# Control_Board_V2.net
KiCad netlist of a schematic drawn in EAGLE
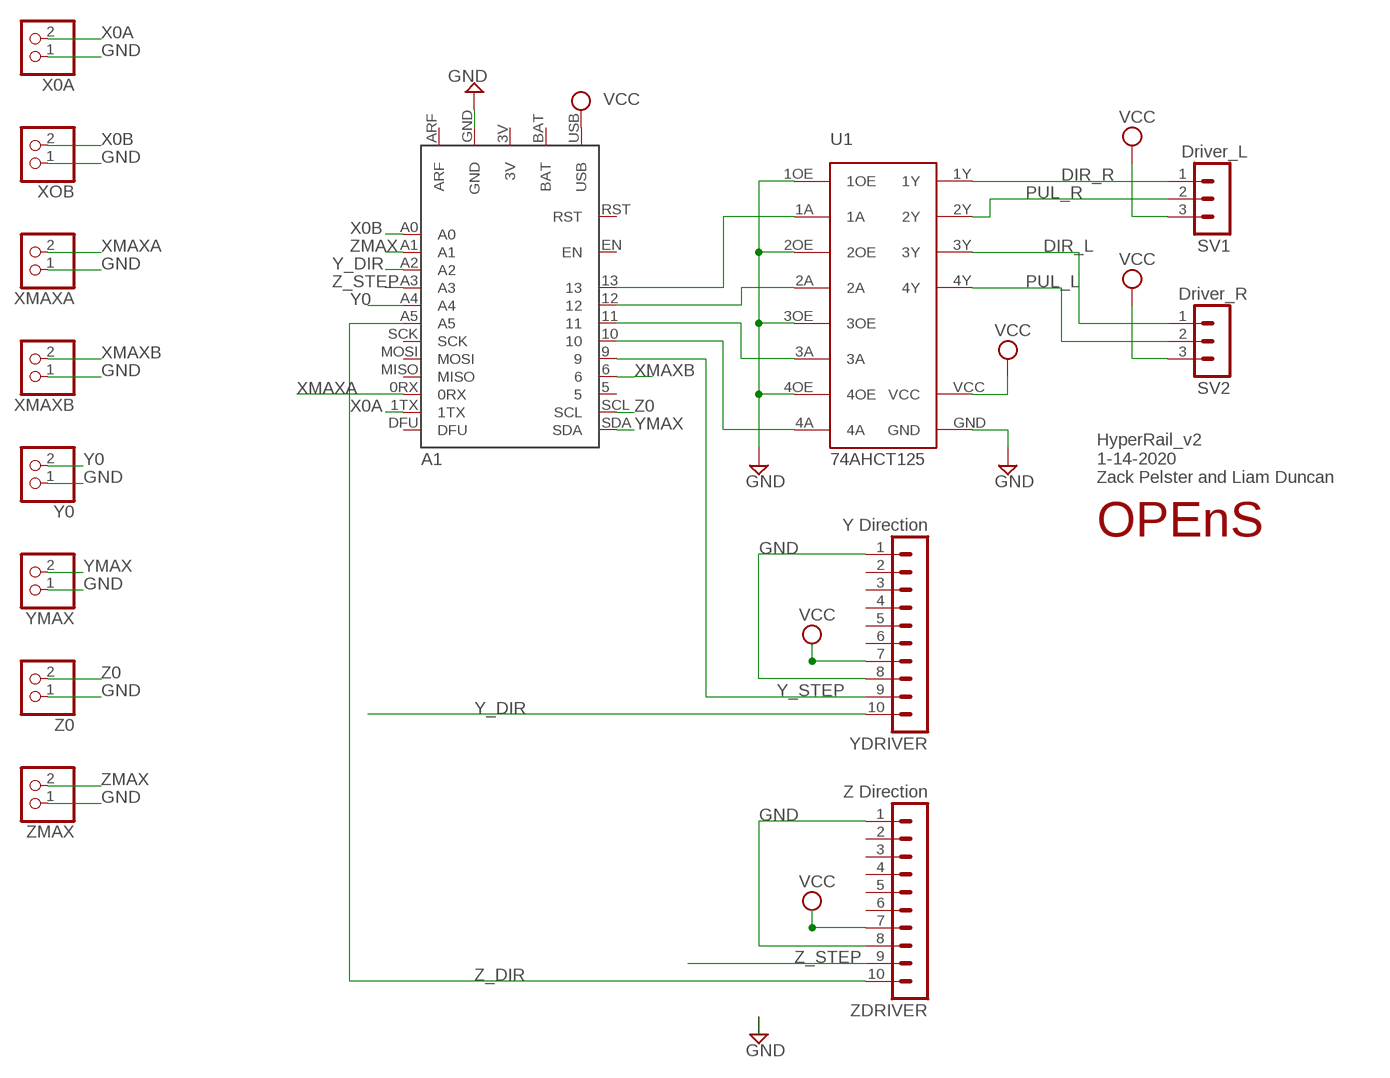
[diagram p0: schematic, sheet 1]

(export (version "E")
  (design (tool "Eeschema 10.0.6"))
  (components
    (comp (ref "A1")
      (value "FEATHER_BLUEFRUIT_M0")
      (footprint "eagle-import:FEATHER_BLUEFRUIT_M0")
      (libsource (lib "eagle-import") (part "FEATHER_BLUEFRUIT_M0"))
    )
    (comp (ref "SV1")
      (value "Driver_L")
      (footprint "eagle-import:MA03-1")
      (libsource (lib "eagle-import") (part "MA03-1"))
    )
    (comp (ref "SV2")
      (value "Driver_R")
      (footprint "eagle-import:MA03-1")
      (libsource (lib "eagle-import") (part "MA03-1"))
    )
    (comp (ref "U$1")
      (value "OPENS-LOGO")
      (footprint "eagle-import:OPENS-LOGO")
      (libsource (lib "eagle-import") (part "OPENS-LOGO"))
    )
    (comp (ref "U1")
      (value "74AHCT125")
      (footprint "eagle-import:74AHCT125")
      (libsource (lib "eagle-import") (part "74AHCT125"))
    )
    (comp (ref "X0A")
      (value "PINHD-1X2")
      (footprint "eagle-import:1X02")
      (libsource (lib "eagle-import") (part "PINHD-1X2"))
    )
    (comp (ref "XMAXA")
      (value "PINHD-1X2")
      (footprint "eagle-import:1X02")
      (libsource (lib "eagle-import") (part "PINHD-1X2"))
    )
    (comp (ref "XMAXB")
      (value "PINHD-1X2")
      (footprint "eagle-import:1X02")
      (libsource (lib "eagle-import") (part "PINHD-1X2"))
    )
    (comp (ref "XOB")
      (value "PINHD-1X2")
      (footprint "eagle-import:1X02")
      (libsource (lib "eagle-import") (part "PINHD-1X2"))
    )
    (comp (ref "Y0")
      (value "PINHD-1X2")
      (footprint "eagle-import:1X02")
      (libsource (lib "eagle-import") (part "PINHD-1X2"))
    )
    (comp (ref "YDRIVER")
      (value "Y Direction")
      (footprint "eagle-import:MA10-1")
      (libsource (lib "eagle-import") (part "MA10-1"))
    )
    (comp (ref "YMAX")
      (value "PINHD-1X2")
      (footprint "eagle-import:1X02")
      (libsource (lib "eagle-import") (part "PINHD-1X2"))
    )
    (comp (ref "Z0")
      (value "PINHD-1X2")
      (footprint "eagle-import:1X02")
      (libsource (lib "eagle-import") (part "PINHD-1X2"))
    )
    (comp (ref "ZDRIVER")
      (value "Z Direction")
      (footprint "eagle-import:MA10-1")
      (libsource (lib "eagle-import") (part "MA10-1"))
    )
    (comp (ref "ZMAX")
      (value "PINHD-1X2")
      (footprint "eagle-import:1X02")
      (libsource (lib "eagle-import") (part "PINHD-1X2"))
    )
  )
  (nets
    (net (code "1") (name "/3V") (class "Default")
      (node (ref "A1") (pin "3V") (pinfunction "3V_3V") (pintype "power_in"))
    )
    (net (code "2") (name "/BAT") (class "Default")
      (node (ref "A1") (pin "BAT") (pinfunction "BAT_BAT") (pintype "power_in"))
    )
    (net (code "3") (name "/DIR_L") (class "Default")
      (node (ref "SV2") (pin "1") (pinfunction "1_1") (pintype "passive"))
      (node (ref "U1") (pin "3Y") (pinfunction "3Y_3Y") (pintype "bidirectional"))
    )
    (net (code "4") (name "/DIR_R") (class "Default")
      (node (ref "SV1") (pin "1") (pinfunction "1_1") (pintype "passive"))
      (node (ref "U1") (pin "1Y") (pinfunction "1Y_1Y") (pintype "bidirectional"))
    )
    (net (code "5") (name "/PUL_L") (class "Default")
      (node (ref "SV2") (pin "2") (pinfunction "2_2") (pintype "passive"))
      (node (ref "U1") (pin "4Y") (pinfunction "4Y_4Y") (pintype "bidirectional"))
    )
    (net (code "6") (name "/PUL_R") (class "Default")
      (node (ref "SV1") (pin "2") (pinfunction "2_2") (pintype "passive"))
      (node (ref "U1") (pin "2Y") (pinfunction "2Y_2Y") (pintype "bidirectional"))
    )
    (net (code "7") (name "/X0A") (class "Default")
      (node (ref "A1") (pin "1TX") (pinfunction "1TX_1TX") (pintype "bidirectional"))
      (node (ref "X0A") (pin "2") (pinfunction "2_2") (pintype "passive"))
    )
    (net (code "8") (name "/X0B") (class "Default")
      (node (ref "A1") (pin "A0") (pinfunction "A0_A0") (pintype "bidirectional"))
      (node (ref "XOB") (pin "2") (pinfunction "2_2") (pintype "passive"))
    )
    (net (code "9") (name "/XMAXA") (class "Default")
      (node (ref "A1") (pin "0RX") (pinfunction "0RX_0RX") (pintype "bidirectional"))
      (node (ref "XMAXA") (pin "2") (pinfunction "2_2") (pintype "passive"))
    )
    (net (code "10") (name "/XMAXB") (class "Default")
      (node (ref "A1") (pin "6") (pinfunction "6_6") (pintype "bidirectional"))
      (node (ref "XMAXB") (pin "2") (pinfunction "2_2") (pintype "passive"))
    )
    (net (code "11") (name "/Y0") (class "Default")
      (node (ref "A1") (pin "A4") (pinfunction "A4_A4") (pintype "bidirectional"))
      (node (ref "Y0") (pin "2") (pinfunction "2_2") (pintype "passive"))
    )
    (net (code "12") (name "/YMAX") (class "Default")
      (node (ref "A1") (pin "SDA") (pinfunction "SDA_SDA") (pintype "bidirectional"))
      (node (ref "YMAX") (pin "2") (pinfunction "2_2") (pintype "passive"))
    )
    (net (code "13") (name "/Y_DIR") (class "Default")
      (node (ref "A1") (pin "A2") (pinfunction "A2_A2") (pintype "bidirectional"))
      (node (ref "YDRIVER") (pin "10") (pinfunction "10_10") (pintype "passive"))
    )
    (net (code "14") (name "/Y_STEP") (class "Default")
      (node (ref "A1") (pin "9") (pinfunction "9_9") (pintype "bidirectional"))
      (node (ref "YDRIVER") (pin "9") (pinfunction "9_9") (pintype "passive"))
    )
    (net (code "15") (name "/Z0") (class "Default")
      (node (ref "A1") (pin "SCL") (pinfunction "SCL_SCL") (pintype "bidirectional"))
      (node (ref "Z0") (pin "2") (pinfunction "2_2") (pintype "passive"))
    )
    (net (code "16") (name "/ZMAX") (class "Default")
      (node (ref "A1") (pin "A1") (pinfunction "A1_A1") (pintype "bidirectional"))
      (node (ref "ZMAX") (pin "2") (pinfunction "2_2") (pintype "passive"))
    )
    (net (code "17") (name "/Z_DIR") (class "Default")
      (node (ref "A1") (pin "A5") (pinfunction "A5_A5") (pintype "bidirectional"))
      (node (ref "ZDRIVER") (pin "10") (pinfunction "10_10") (pintype "passive"))
    )
    (net (code "18") (name "/Z_STEP") (class "Default")
      (node (ref "A1") (pin "A3") (pinfunction "A3_A3") (pintype "bidirectional"))
      (node (ref "ZDRIVER") (pin "9") (pinfunction "9_9") (pintype "passive"))
    )
    (net (code "19") (name "GND") (class "Default")
      (node (ref "A1") (pin "GND") (pinfunction "GND_GND") (pintype "power_in"))
      (node (ref "U1") (pin "1OE") (pinfunction "1OE_1OE") (pintype "bidirectional"))
      (node (ref "U1") (pin "2OE") (pinfunction "2OE_2OE") (pintype "bidirectional"))
      (node (ref "U1") (pin "3OE") (pinfunction "3OE_3OE") (pintype "bidirectional"))
      (node (ref "U1") (pin "4OE") (pinfunction "4OE_4OE") (pintype "bidirectional"))
      (node (ref "U1") (pin "GND") (pinfunction "GND_GND") (pintype "bidirectional"))
      (node (ref "X0A") (pin "1") (pinfunction "1_1") (pintype "passive"))
      (node (ref "XMAXA") (pin "1") (pinfunction "1_1") (pintype "passive"))
      (node (ref "XMAXB") (pin "1") (pinfunction "1_1") (pintype "passive"))
      (node (ref "XOB") (pin "1") (pinfunction "1_1") (pintype "passive"))
      (node (ref "Y0") (pin "1") (pinfunction "1_1") (pintype "passive"))
      (node (ref "YDRIVER") (pin "1") (pinfunction "1_1") (pintype "passive"))
      (node (ref "YDRIVER") (pin "8") (pinfunction "8_8") (pintype "passive"))
      (node (ref "YMAX") (pin "1") (pinfunction "1_1") (pintype "passive"))
      (node (ref "Z0") (pin "1") (pinfunction "1_1") (pintype "passive"))
      (node (ref "ZDRIVER") (pin "1") (pinfunction "1_1") (pintype "passive"))
      (node (ref "ZDRIVER") (pin "8") (pinfunction "8_8") (pintype "passive"))
      (node (ref "ZMAX") (pin "1") (pinfunction "1_1") (pintype "passive"))
    )
    (net (code "20") (name "Net-(A1-Pad10)") (class "Default")
      (node (ref "A1") (pin "10") (pinfunction "10_10") (pintype "bidirectional"))
      (node (ref "U1") (pin "4A") (pinfunction "4A_4A") (pintype "bidirectional"))
    )
    (net (code "21") (name "Net-(A1-Pad11)") (class "Default")
      (node (ref "A1") (pin "11") (pinfunction "11_11") (pintype "bidirectional"))
      (node (ref "U1") (pin "3A") (pinfunction "3A_3A") (pintype "bidirectional"))
    )
    (net (code "22") (name "Net-(A1-Pad12)") (class "Default")
      (node (ref "A1") (pin "12") (pinfunction "12_12") (pintype "bidirectional"))
      (node (ref "U1") (pin "2A") (pinfunction "2A_2A") (pintype "bidirectional"))
    )
    (net (code "23") (name "Net-(A1-Pad13)") (class "Default")
      (node (ref "A1") (pin "13") (pinfunction "13_13") (pintype "bidirectional"))
      (node (ref "U1") (pin "1A") (pinfunction "1A_1A") (pintype "bidirectional"))
    )
    (net (code "24") (name "VCC") (class "Default")
      (node (ref "A1") (pin "USB") (pinfunction "USB_USB") (pintype "power_in"))
      (node (ref "SV1") (pin "3") (pinfunction "3_3") (pintype "passive"))
      (node (ref "SV2") (pin "3") (pinfunction "3_3") (pintype "passive"))
      (node (ref "U1") (pin "VCC") (pinfunction "VCC_VCC") (pintype "bidirectional"))
      (node (ref "YDRIVER") (pin "7") (pinfunction "7_7") (pintype "passive"))
      (node (ref "ZDRIVER") (pin "7") (pinfunction "7_7") (pintype "passive"))
    )
    (net (code "25") (name "unconnected-(A1-Pad5)") (class "Default")
      (node (ref "A1") (pin "5") (pinfunction "5_5") (pintype "bidirectional"))
    )
    (net (code "26") (name "unconnected-(A1-PadARF)") (class "Default")
      (node (ref "A1") (pin "ARF") (pinfunction "ARF_ARF") (pintype "bidirectional"))
    )
    (net (code "27") (name "unconnected-(A1-PadDFU)") (class "Default")
      (node (ref "A1") (pin "DFU") (pinfunction "DFU_DFU") (pintype "bidirectional"))
    )
    (net (code "28") (name "unconnected-(A1-PadEN)") (class "Default")
      (node (ref "A1") (pin "EN") (pinfunction "EN_EN") (pintype "bidirectional"))
    )
    (net (code "29") (name "unconnected-(A1-PadMISO)") (class "Default")
      (node (ref "A1") (pin "MISO") (pinfunction "MISO_MISO") (pintype "bidirectional"))
    )
    (net (code "30") (name "unconnected-(A1-PadMOSI)") (class "Default")
      (node (ref "A1") (pin "MOSI") (pinfunction "MOSI_MOSI") (pintype "bidirectional"))
    )
    (net (code "31") (name "unconnected-(A1-PadRST)") (class "Default")
      (node (ref "A1") (pin "RST") (pinfunction "RST_RST") (pintype "bidirectional"))
    )
    (net (code "32") (name "unconnected-(A1-PadSCK)") (class "Default")
      (node (ref "A1") (pin "SCK") (pinfunction "SCK_SCK") (pintype "bidirectional"))
    )
    (net (code "33") (name "unconnected-(YDRIVER-Pad2)") (class "Default")
      (node (ref "YDRIVER") (pin "2") (pinfunction "2_2") (pintype "passive"))
    )
    (net (code "34") (name "unconnected-(YDRIVER-Pad3)") (class "Default")
      (node (ref "YDRIVER") (pin "3") (pinfunction "3_3") (pintype "passive"))
    )
    (net (code "35") (name "unconnected-(YDRIVER-Pad4)") (class "Default")
      (node (ref "YDRIVER") (pin "4") (pinfunction "4_4") (pintype "passive"))
    )
    (net (code "36") (name "unconnected-(YDRIVER-Pad5)") (class "Default")
      (node (ref "YDRIVER") (pin "5") (pinfunction "5_5") (pintype "passive"))
    )
    (net (code "37") (name "unconnected-(YDRIVER-Pad6)") (class "Default")
      (node (ref "YDRIVER") (pin "6") (pinfunction "6_6") (pintype "passive"))
    )
    (net (code "38") (name "unconnected-(ZDRIVER-Pad2)") (class "Default")
      (node (ref "ZDRIVER") (pin "2") (pinfunction "2_2") (pintype "passive"))
    )
    (net (code "39") (name "unconnected-(ZDRIVER-Pad3)") (class "Default")
      (node (ref "ZDRIVER") (pin "3") (pinfunction "3_3") (pintype "passive"))
    )
    (net (code "40") (name "unconnected-(ZDRIVER-Pad4)") (class "Default")
      (node (ref "ZDRIVER") (pin "4") (pinfunction "4_4") (pintype "passive"))
    )
    (net (code "41") (name "unconnected-(ZDRIVER-Pad5)") (class "Default")
      (node (ref "ZDRIVER") (pin "5") (pinfunction "5_5") (pintype "passive"))
    )
    (net (code "42") (name "unconnected-(ZDRIVER-Pad6)") (class "Default")
      (node (ref "ZDRIVER") (pin "6") (pinfunction "6_6") (pintype "passive"))
    )
  )
)
